# GLV-Connectors.net
KiCad netlist of a schematic drawn in Altium Designer
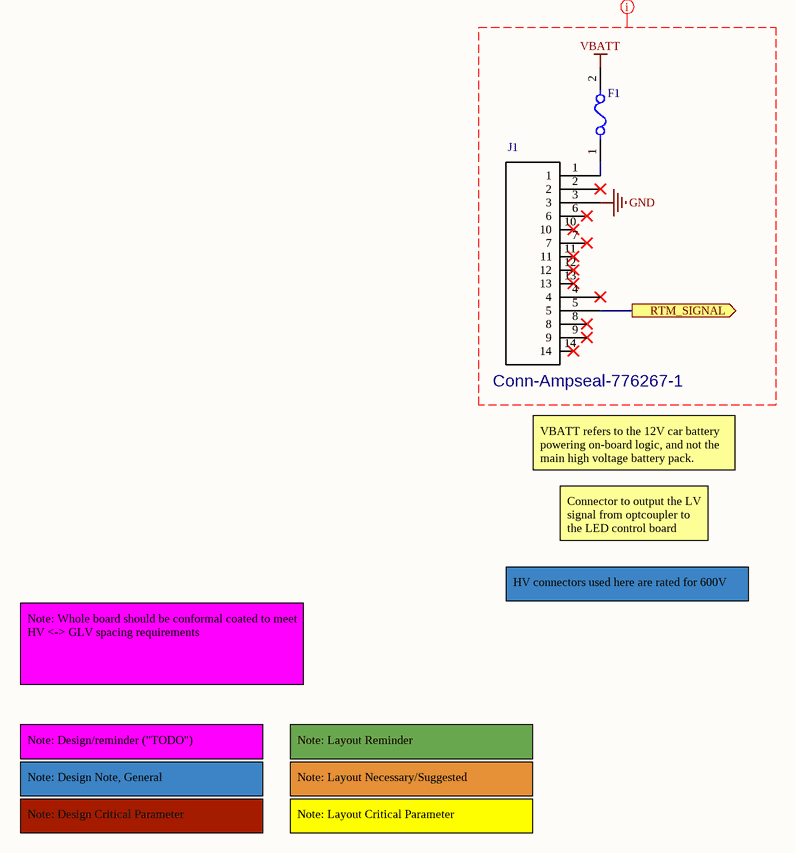
[diagram p0: GLV-Connectors.SchDoc]

(export (version "E")
  (design (tool "Eeschema 10.0.6"))
  (components
    (comp (ref "F1")
      (value "0468003.NRHF")
      (footprint "FP-437-MFG")
      (description "FUSE BRD MNT 3A 32VAC 35VDC 1206")
      (fields
        (field (name "OCTOPART") "https://octopart.com/0437003.wr-littelfuse-8600121")
        (field (name "MANUFACTURER") "Littelfuse Inc")
      )
      (libsource (lib "Altium Content Vault") (part "5bcf9b9f640e542cf0359d10258e979"))
    )
    (comp (ref "J1")
      (value "Conn-Ampseal-776267-1")
      (footprint "FOOTPRINT-AMPSEAL-776267-1")
      (description "AMPSEAL RA 14ckt Faced w/ Gasket Automotive")
      (fields (field (name "MP") "776267-1") (field (name "MF") "TE Connectivity"))
      (libsource (lib "University of California Riverside - FSAE") (part "Conn-Ampseal-776267-1"))
    )
  )
  (nets
    (net (code "1") (name "/RTM_SIGNAL") (class "Default")
      (node (ref "J1") (pin "5") (pinfunction "5_5") (pintype "passive"))
    )
    (net (code "2") (name "GND") (class "Default")
      (node (ref "J1") (pin "3") (pinfunction "3_3") (pintype "passive"))
    )
    (net (code "3") (name "Net-(F1-Pad1)") (class "Default")
      (node (ref "F1") (pin "1") (pinfunction "1_1") (pintype "passive"))
      (node (ref "J1") (pin "1") (pinfunction "1_1") (pintype "passive"))
    )
    (net (code "4") (name "VBATT") (class "Default")
      (node (ref "F1") (pin "2") (pinfunction "2_2") (pintype "passive"))
    )
    (net (code "5") (name "unconnected-(J1-Pad2)") (class "Default")
      (node (ref "J1") (pin "2") (pinfunction "2_2") (pintype "passive+no_connect"))
    )
    (net (code "6") (name "unconnected-(J1-Pad4)") (class "Default")
      (node (ref "J1") (pin "4") (pinfunction "4_4") (pintype "passive+no_connect"))
    )
    (net (code "7") (name "unconnected-(J1-Pad6)") (class "Default")
      (node (ref "J1") (pin "6") (pinfunction "6_6") (pintype "passive+no_connect"))
    )
    (net (code "8") (name "unconnected-(J1-Pad7)") (class "Default")
      (node (ref "J1") (pin "7") (pinfunction "7_7") (pintype "passive+no_connect"))
    )
    (net (code "9") (name "unconnected-(J1-Pad8)") (class "Default")
      (node (ref "J1") (pin "8") (pinfunction "8_8") (pintype "passive+no_connect"))
    )
    (net (code "10") (name "unconnected-(J1-Pad9)") (class "Default")
      (node (ref "J1") (pin "9") (pinfunction "9_9") (pintype "passive+no_connect"))
    )
    (net (code "11") (name "unconnected-(J1-Pad10)") (class "Default")
      (node (ref "J1") (pin "10") (pinfunction "10_10") (pintype "passive+no_connect"))
    )
    (net (code "12") (name "unconnected-(J1-Pad11)") (class "Default")
      (node (ref "J1") (pin "11") (pinfunction "11_11") (pintype "passive+no_connect"))
    )
    (net (code "13") (name "unconnected-(J1-Pad12)") (class "Default")
      (node (ref "J1") (pin "12") (pinfunction "12_12") (pintype "passive+no_connect"))
    )
    (net (code "14") (name "unconnected-(J1-Pad13)") (class "Default")
      (node (ref "J1") (pin "13") (pinfunction "13_13") (pintype "passive+no_connect"))
    )
    (net (code "15") (name "unconnected-(J1-Pad14)") (class "Default")
      (node (ref "J1") (pin "14") (pinfunction "14_14") (pintype "passive+no_connect"))
    )
  )
)
